# power_supply_unit.net
KiCad netlist of a schematic drawn in EAGLE
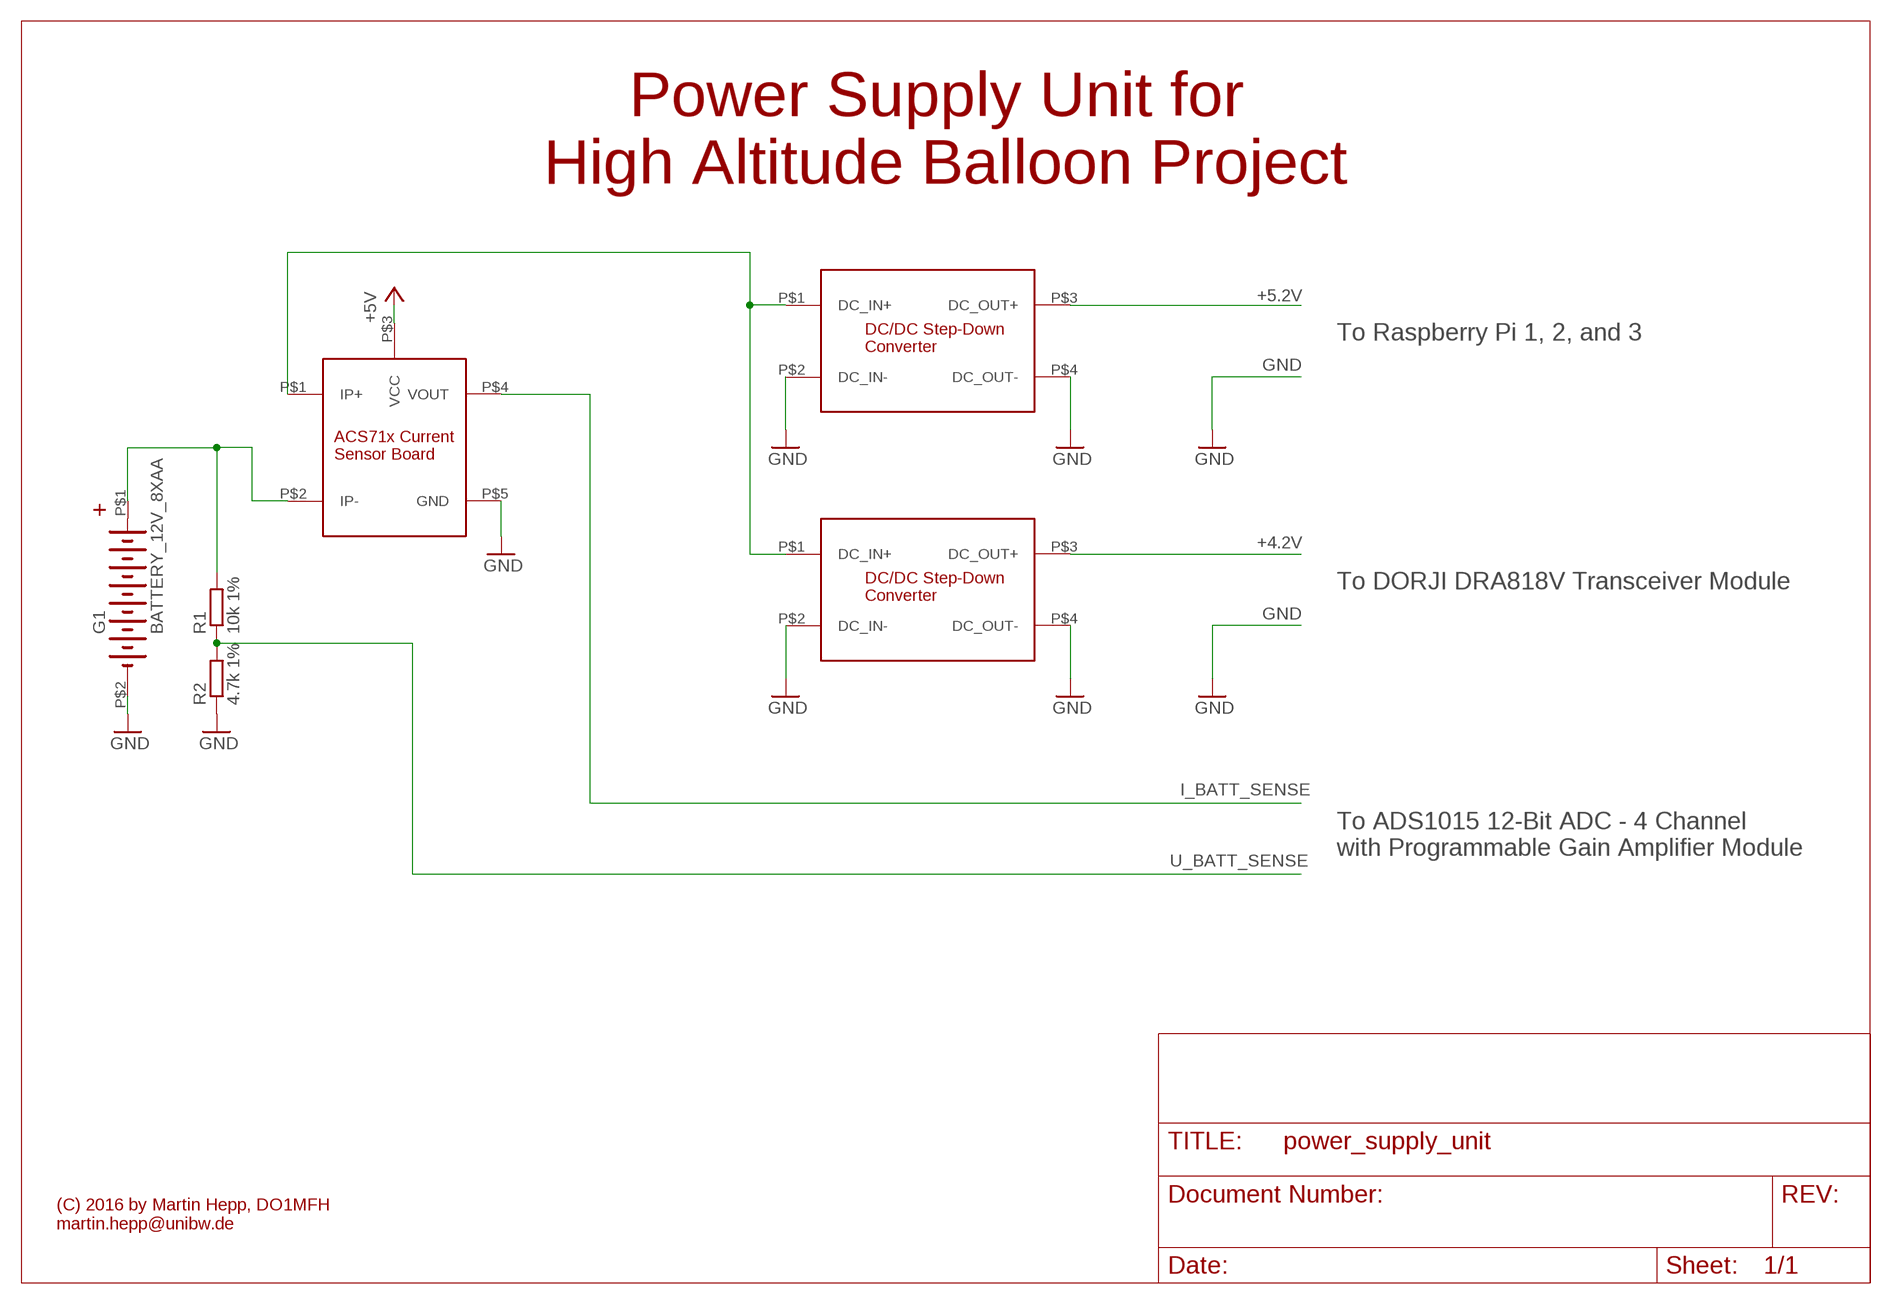
[diagram p0: schematic, sheet 1]

(export (version "E")
  (design (tool "Eeschema 10.0.6"))
  (components
    (comp (ref "G1")
      (value "BATTERY_12V_8XAA")
      (footprint "eagle-import:BATTERY_12V_8XAA")
      (libsource (lib "eagle-import") (part "BATTERY_12V_8XAA"))
    )
    (comp (ref "R1")
      (value "10k 1%")
      (footprint "eagle-import:0207_10")
      (libsource (lib "eagle-import") (part "R-EU_0207/10"))
    )
    (comp (ref "R2")
      (value "4.7k 1%")
      (footprint "eagle-import:0207_10")
      (libsource (lib "eagle-import") (part "R-EU_0207/10"))
    )
    (comp (ref "U$1")
      (value "STEP_DOWN_CONVERTER")
      (footprint "eagle-import:DUMMY_PACKAGE")
      (libsource (lib "eagle-import") (part "STEP_DOWN_CONVERTER"))
    )
    (comp (ref "U$2")
      (value "STEP_DOWN_CONVERTER")
      (footprint "eagle-import:DUMMY_PACKAGE")
      (libsource (lib "eagle-import") (part "STEP_DOWN_CONVERTER"))
    )
    (comp (ref "U$3")
      (value "ACS71X_CURRENT_SENSOR")
      (footprint "eagle-import:DUMMY_PACKAGE2")
      (libsource (lib "eagle-import") (part "ACS71X_CURRENT_SENSOR"))
    )
  )
  (nets
    (net (code "1") (name "+5V") (class "Default")
      (node (ref "U$3") (pin "P$3") (pinfunction "VCC_P$3") (pintype "bidirectional"))
    )
    (net (code "4") (name "/I_BATT_SENSE") (class "Default")
      (node (ref "U$3") (pin "P$4") (pinfunction "VOUT_P$4") (pintype "bidirectional"))
    )
    (net (code "5") (name "/U_BATT_SENSE") (class "Default")
      (node (ref "R1") (pin "1") (pinfunction "1_1") (pintype "passive"))
      (node (ref "R2") (pin "2") (pinfunction "2_2") (pintype "passive"))
    )
    (net (code "6") (name "GND") (class "Default")
      (node (ref "G1") (pin "P$2") (pinfunction "-_P$2") (pintype "passive"))
      (node (ref "R2") (pin "1") (pinfunction "1_1") (pintype "passive"))
      (node (ref "U$3") (pin "P$5") (pinfunction "GND_P$5") (pintype "bidirectional"))
    )
    (net (code "7") (name "Net-(G1-+)") (class "Default")
      (node (ref "G1") (pin "P$1") (pinfunction "+_P$1") (pintype "passive"))
      (node (ref "R1") (pin "2") (pinfunction "2_2") (pintype "passive"))
      (node (ref "U$3") (pin "P$2") (pinfunction "IP-_P$2") (pintype "bidirectional"))
    )
    (net (code "8") (name "unconnected-(U$1-DC_IN+-PadP$1)") (class "Default")
      (node (ref "U$1") (pin "P$1") (pinfunction "DC_IN+_P$1") (pintype "bidirectional"))
    )
    (net (code "9") (name "unconnected-(U$1-DC_IN--PadP$2)") (class "Default")
      (node (ref "U$1") (pin "P$2") (pinfunction "DC_IN-_P$2") (pintype "bidirectional"))
    )
    (net (code "10") (name "unconnected-(U$1-DC_OUT+-PadP$3)") (class "Default")
      (node (ref "U$1") (pin "P$3") (pinfunction "DC_OUT+_P$3") (pintype "bidirectional"))
    )
    (net (code "11") (name "unconnected-(U$1-DC_OUT--PadP$4)") (class "Default")
      (node (ref "U$1") (pin "P$4") (pinfunction "DC_OUT-_P$4") (pintype "bidirectional"))
    )
    (net (code "12") (name "unconnected-(U$2-DC_IN+-PadP$1)") (class "Default")
      (node (ref "U$2") (pin "P$1") (pinfunction "DC_IN+_P$1") (pintype "bidirectional"))
    )
    (net (code "13") (name "unconnected-(U$2-DC_IN--PadP$2)") (class "Default")
      (node (ref "U$2") (pin "P$2") (pinfunction "DC_IN-_P$2") (pintype "bidirectional"))
    )
    (net (code "14") (name "unconnected-(U$2-DC_OUT+-PadP$3)") (class "Default")
      (node (ref "U$2") (pin "P$3") (pinfunction "DC_OUT+_P$3") (pintype "bidirectional"))
    )
    (net (code "15") (name "unconnected-(U$2-DC_OUT--PadP$4)") (class "Default")
      (node (ref "U$2") (pin "P$4") (pinfunction "DC_OUT-_P$4") (pintype "bidirectional"))
    )
    (net (code "16") (name "unconnected-(U$3-IP+-PadP$1)") (class "Default")
      (node (ref "U$3") (pin "P$1") (pinfunction "IP+_P$1") (pintype "bidirectional"))
    )
  )
)
